# duobackpane.net
KiCad netlist of a schematic drawn in EAGLE
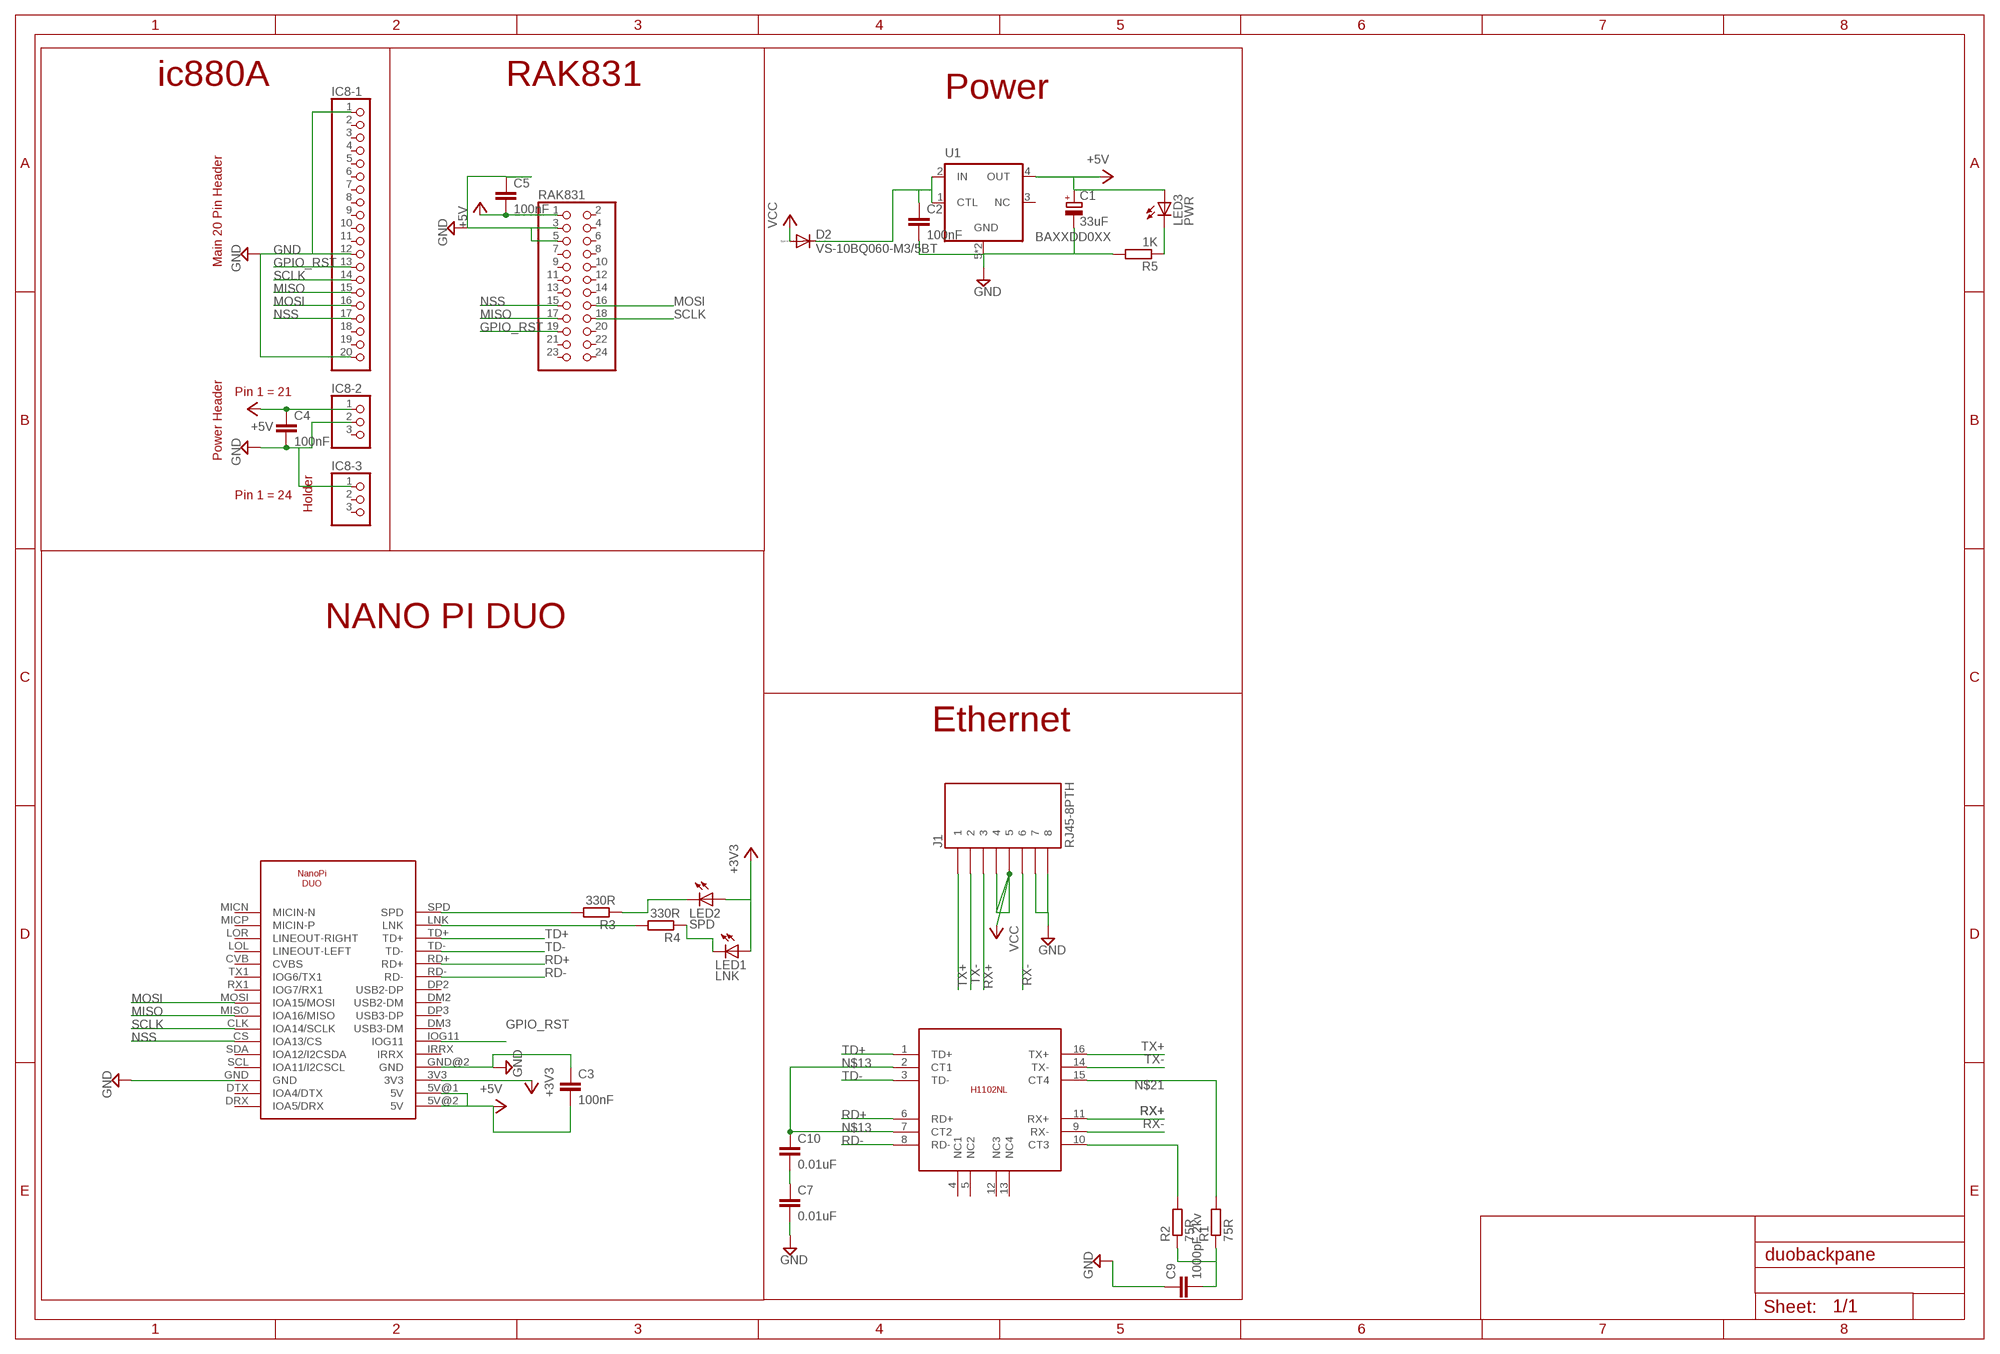
[diagram p0: schematic, sheet 1]

(export (version "E")
  (design (tool "Eeschema 10.0.6"))
  (components
    (comp (ref "C1")
      (value "33uF")
      (footprint "eagle-import:SMC_A")
      (libsource (lib "eagle-import") (part "CPOL-EUSMCA"))
    )
    (comp (ref "C2")
      (value "100nF")
      (footprint "eagle-import:C0805")
      (libsource (lib "eagle-import") (part "C-EUC0805"))
    )
    (comp (ref "C3")
      (value "100nF")
      (footprint "eagle-import:C0805")
      (libsource (lib "eagle-import") (part "C-EUC0805"))
    )
    (comp (ref "C4")
      (value "100nF")
      (footprint "eagle-import:C0805")
      (libsource (lib "eagle-import") (part "C-EUC0805"))
    )
    (comp (ref "C5")
      (value "100nF")
      (footprint "eagle-import:C0805")
      (libsource (lib "eagle-import") (part "C-EUC0805"))
    )
    (comp (ref "C7")
      (value "0.01uF")
      (footprint "eagle-import:C0805")
      (libsource (lib "eagle-import") (part "C-EUC0805"))
    )
    (comp (ref "C9")
      (value "1000pF 2kv")
      (footprint "eagle-import:C1206")
      (libsource (lib "eagle-import") (part "C-EUC1206"))
    )
    (comp (ref "C10")
      (value "0.01uF")
      (footprint "eagle-import:C0805")
      (libsource (lib "eagle-import") (part "C-EUC0805"))
    )
    (comp (ref "D2")
      (value "VS-10BQ060-M3/5BT")
      (footprint "eagle-import:DO214AA")
      (libsource (lib "eagle-import") (part "DIODE-DO214AA"))
    )
    (comp (ref "IC8-1")
      (value "PINHD-1X20")
      (footprint "eagle-import:1X20")
      (libsource (lib "eagle-import") (part "PINHD-1X20"))
    )
    (comp (ref "IC8-2")
      (value "PINHD-1X3")
      (footprint "eagle-import:1X03")
      (libsource (lib "eagle-import") (part "PINHD-1X3"))
    )
    (comp (ref "IC8-3")
      (value "PINHD-1X3")
      (footprint "eagle-import:1X03")
      (libsource (lib "eagle-import") (part "PINHD-1X3"))
    )
    (comp (ref "J1")
      (value "RJ45-8PTH")
      (footprint "eagle-import:RJ45-8")
      (libsource (lib "eagle-import") (part "RJ45-8PTH"))
    )
    (comp (ref "LED1")
      (value "LNK")
      (footprint "eagle-import:SML1206")
      (libsource (lib "eagle-import") (part "LEDSML1206"))
    )
    (comp (ref "LED2")
      (value "SPD")
      (footprint "eagle-import:SML1206")
      (libsource (lib "eagle-import") (part "LEDSML1206"))
    )
    (comp (ref "LED3")
      (value "PWR")
      (footprint "eagle-import:SML1206")
      (libsource (lib "eagle-import") (part "LEDSML1206"))
    )
    (comp (ref "R1")
      (value "75R")
      (footprint "eagle-import:R0805")
      (libsource (lib "eagle-import") (part "R-EU_R0805"))
    )
    (comp (ref "R2")
      (value "75R")
      (footprint "eagle-import:R0805")
      (libsource (lib "eagle-import") (part "R-EU_R0805"))
    )
    (comp (ref "R3")
      (value "330R")
      (footprint "eagle-import:R0805")
      (libsource (lib "eagle-import") (part "R-EU_R0805"))
    )
    (comp (ref "R4")
      (value "330R")
      (footprint "eagle-import:R0805")
      (libsource (lib "eagle-import") (part "R-EU_R0805"))
    )
    (comp (ref "R5")
      (value "1K")
      (footprint "eagle-import:R0805")
      (libsource (lib "eagle-import") (part "R-EU_R0805"))
    )
    (comp (ref "RAK831")
      (value "PINHD-2X12")
      (footprint "eagle-import:2X12")
      (libsource (lib "eagle-import") (part "PINHD-2X12"))
    )
    (comp (ref "U$1")
      (value "DECADE-H1102NL")
      (footprint "eagle-import:DECADE-H1102NL")
      (libsource (lib "eagle-import") (part "DECADE-H1102NL"))
    )
    (comp (ref "U$2")
      (value "NANOPIDUO")
      (footprint "eagle-import:NANOPIDUO")
      (libsource (lib "eagle-import") (part "NANOPIDUO"))
    )
    (comp (ref "U1")
      (value "BAXXDD0XX")
      (footprint "eagle-import:HRP5")
      (libsource (lib "eagle-import") (part "BAXXDD0XX"))
    )
  )
  (nets
    (net (code "1") (name "+3V3") (class "Default")
      (node (ref "LED1") (pin "A") (pinfunction "A_A") (pintype "passive"))
      (node (ref "LED2") (pin "A") (pinfunction "A_A") (pintype "passive"))
      (node (ref "U$2") (pin "3V3") (pinfunction "3V3_3V3") (pintype "bidirectional"))
    )
    (net (code "2") (name "+5V") (class "Default")
      (node (ref "C1") (pin "+") (pinfunction "+_+") (pintype "passive"))
      (node (ref "C3") (pin "2") (pinfunction "2_2") (pintype "passive"))
      (node (ref "C4") (pin "1") (pinfunction "1_1") (pintype "passive"))
      (node (ref "C5") (pin "2") (pinfunction "2_2") (pintype "passive"))
      (node (ref "IC8-2") (pin "1") (pinfunction "1_1") (pintype "passive"))
      (node (ref "LED3") (pin "A") (pinfunction "A_A") (pintype "passive"))
      (node (ref "RAK831") (pin "1") (pinfunction "1_1") (pintype "passive"))
      (node (ref "U$2") (pin "5V@1") (pinfunction "5V_5V@1") (pintype "bidirectional"))
      (node (ref "U$2") (pin "5V@2") (pinfunction "5V_5V@2") (pintype "bidirectional"))
      (node (ref "U1") (pin "4") (pinfunction "OUT_4") (pintype "passive"))
    )
    (net (code "3") (name "/GPIO_RST") (class "Default")
      (node (ref "IC8-1") (pin "13") (pinfunction "13_13") (pintype "passive"))
      (node (ref "RAK831") (pin "19") (pinfunction "19_19") (pintype "passive"))
      (node (ref "U$2") (pin "IOG11") (pinfunction "IOG11_IOG11") (pintype "bidirectional"))
    )
    (net (code "4") (name "/MISO") (class "Default")
      (node (ref "IC8-1") (pin "15") (pinfunction "15_15") (pintype "passive"))
      (node (ref "RAK831") (pin "17") (pinfunction "17_17") (pintype "passive"))
      (node (ref "U$2") (pin "MISO") (pinfunction "IOA16/MISO_MISO") (pintype "bidirectional"))
    )
    (net (code "5") (name "/MOSI") (class "Default")
      (node (ref "IC8-1") (pin "16") (pinfunction "16_16") (pintype "passive"))
      (node (ref "RAK831") (pin "16") (pinfunction "16_16") (pintype "passive"))
      (node (ref "U$2") (pin "MOSI") (pinfunction "IOA15/MOSI_MOSI") (pintype "bidirectional"))
    )
    (net (code "6") (name "/N$13") (class "Default")
      (node (ref "C10") (pin "1") (pinfunction "1_1") (pintype "passive"))
      (node (ref "U$1") (pin "2") (pinfunction "CT1_2") (pintype "bidirectional"))
      (node (ref "U$1") (pin "7") (pinfunction "CT2_7") (pintype "bidirectional"))
    )
    (net (code "7") (name "/N$21") (class "Default")
      (node (ref "R1") (pin "2") (pinfunction "2_2") (pintype "passive"))
      (node (ref "U$1") (pin "15") (pinfunction "CT4_15") (pintype "bidirectional"))
    )
    (net (code "8") (name "/NSS") (class "Default")
      (node (ref "IC8-1") (pin "17") (pinfunction "17_17") (pintype "passive"))
      (node (ref "RAK831") (pin "15") (pinfunction "15_15") (pintype "passive"))
      (node (ref "U$2") (pin "CS") (pinfunction "IOA13/CS_CS") (pintype "bidirectional"))
    )
    (net (code "9") (name "/RD+") (class "Default")
      (node (ref "U$1") (pin "6") (pinfunction "RD+_6") (pintype "bidirectional"))
      (node (ref "U$2") (pin "RD+") (pinfunction "RD+_RD+") (pintype "bidirectional"))
    )
    (net (code "10") (name "/RD-") (class "Default")
      (node (ref "U$1") (pin "8") (pinfunction "RD-_8") (pintype "bidirectional"))
      (node (ref "U$2") (pin "RD-") (pinfunction "RD-_RD-") (pintype "bidirectional"))
    )
    (net (code "11") (name "/RX+") (class "Default")
      (node (ref "J1") (pin "3") (pinfunction "3_3") (pintype "bidirectional"))
      (node (ref "U$1") (pin "11") (pinfunction "RX+_11") (pintype "bidirectional"))
    )
    (net (code "12") (name "/RX-") (class "Default")
      (node (ref "J1") (pin "6") (pinfunction "6_6") (pintype "bidirectional"))
      (node (ref "U$1") (pin "9") (pinfunction "RX-_9") (pintype "bidirectional"))
    )
    (net (code "13") (name "/SCLK") (class "Default")
      (node (ref "IC8-1") (pin "14") (pinfunction "14_14") (pintype "passive"))
      (node (ref "RAK831") (pin "18") (pinfunction "18_18") (pintype "passive"))
      (node (ref "U$2") (pin "CLK") (pinfunction "IOA14/SCLK_CLK") (pintype "bidirectional"))
    )
    (net (code "14") (name "/TD+") (class "Default")
      (node (ref "U$1") (pin "1") (pinfunction "TD+_1") (pintype "bidirectional"))
      (node (ref "U$2") (pin "TD+") (pinfunction "TD+_TD+") (pintype "bidirectional"))
    )
    (net (code "15") (name "/TD-") (class "Default")
      (node (ref "U$1") (pin "3") (pinfunction "TD-_3") (pintype "bidirectional"))
      (node (ref "U$2") (pin "TD-") (pinfunction "TD-_TD-") (pintype "bidirectional"))
    )
    (net (code "16") (name "/TX+") (class "Default")
      (node (ref "J1") (pin "1") (pinfunction "1_1") (pintype "bidirectional"))
      (node (ref "U$1") (pin "16") (pinfunction "TX+_16") (pintype "bidirectional"))
    )
    (net (code "17") (name "/TX-") (class "Default")
      (node (ref "J1") (pin "2") (pinfunction "2_2") (pintype "bidirectional"))
      (node (ref "U$1") (pin "14") (pinfunction "TX-_14") (pintype "bidirectional"))
    )
    (net (code "18") (name "GND") (class "Default")
      (node (ref "C1") (pin "-") (pinfunction "-_-") (pintype "passive"))
      (node (ref "C2") (pin "2") (pinfunction "2_2") (pintype "passive"))
      (node (ref "C3") (pin "1") (pinfunction "1_1") (pintype "passive"))
      (node (ref "C4") (pin "2") (pinfunction "2_2") (pintype "passive"))
      (node (ref "C5") (pin "1") (pinfunction "1_1") (pintype "passive"))
      (node (ref "C7") (pin "2") (pinfunction "2_2") (pintype "passive"))
      (node (ref "C9") (pin "1") (pinfunction "1_1") (pintype "passive"))
      (node (ref "IC8-1") (pin "1") (pinfunction "1_1") (pintype "passive"))
      (node (ref "IC8-1") (pin "12") (pinfunction "12_12") (pintype "passive"))
      (node (ref "IC8-1") (pin "20") (pinfunction "20_20") (pintype "passive"))
      (node (ref "IC8-2") (pin "2") (pinfunction "2_2") (pintype "passive"))
      (node (ref "IC8-3") (pin "1") (pinfunction "1_1") (pintype "passive"))
      (node (ref "J1") (pin "7") (pinfunction "7_7") (pintype "bidirectional"))
      (node (ref "J1") (pin "8") (pinfunction "8_8") (pintype "bidirectional"))
      (node (ref "R5") (pin "2") (pinfunction "2_2") (pintype "passive"))
      (node (ref "RAK831") (pin "3") (pinfunction "3_3") (pintype "passive"))
      (node (ref "RAK831") (pin "5") (pinfunction "5_5") (pintype "passive"))
      (node (ref "U$2") (pin "GND") (pinfunction "GND_GND") (pintype "bidirectional"))
      (node (ref "U$2") (pin "GND@2") (pinfunction "GND_GND@2") (pintype "bidirectional"))
      (node (ref "U1") (pin "5") (pinfunction "GND_5") (pintype "passive"))
      (node (ref "U1") (pin "6") (pinfunction "GND_6") (pintype "passive"))
    )
    (net (code "19") (name "Net-(C9-Pad2)") (class "Default")
      (node (ref "C9") (pin "2") (pinfunction "2_2") (pintype "passive"))
      (node (ref "R1") (pin "1") (pinfunction "1_1") (pintype "passive"))
      (node (ref "R2") (pin "1") (pinfunction "1_1") (pintype "passive"))
    )
    (net (code "20") (name "Net-(C10-Pad2)") (class "Default")
      (node (ref "C10") (pin "2") (pinfunction "2_2") (pintype "passive"))
      (node (ref "C7") (pin "1") (pinfunction "1_1") (pintype "passive"))
    )
    (net (code "21") (name "Net-(LED1-PadC)") (class "Default")
      (node (ref "LED1") (pin "C") (pinfunction "C_C") (pintype "passive"))
      (node (ref "R4") (pin "1") (pinfunction "1_1") (pintype "passive"))
    )
    (net (code "22") (name "Net-(LED2-PadC)") (class "Default")
      (node (ref "LED2") (pin "C") (pinfunction "C_C") (pintype "passive"))
      (node (ref "R3") (pin "1") (pinfunction "1_1") (pintype "passive"))
    )
    (net (code "23") (name "Net-(LED3-PadC)") (class "Default")
      (node (ref "LED3") (pin "C") (pinfunction "C_C") (pintype "passive"))
      (node (ref "R5") (pin "1") (pinfunction "1_1") (pintype "passive"))
    )
    (net (code "24") (name "Net-(R3-Pad2)") (class "Default")
      (node (ref "R3") (pin "2") (pinfunction "2_2") (pintype "passive"))
      (node (ref "U$2") (pin "SPD") (pinfunction "SPD_SPD") (pintype "bidirectional"))
    )
    (net (code "25") (name "Net-(R4-Pad2)") (class "Default")
      (node (ref "R4") (pin "2") (pinfunction "2_2") (pintype "passive"))
      (node (ref "U$2") (pin "LNK") (pinfunction "LNK_LNK") (pintype "bidirectional"))
    )
    (net (code "26") (name "Net-(U$1-CT3)") (class "Default")
      (node (ref "R2") (pin "2") (pinfunction "2_2") (pintype "passive"))
      (node (ref "U$1") (pin "10") (pinfunction "CT3_10") (pintype "bidirectional"))
    )
    (net (code "27") (name "Net-(U1-CTL)") (class "Default")
      (node (ref "C2") (pin "1") (pinfunction "1_1") (pintype "passive"))
      (node (ref "D2") (pin "C") (pinfunction "C_C") (pintype "passive"))
      (node (ref "U1") (pin "1") (pinfunction "CTL_1") (pintype "input"))
      (node (ref "U1") (pin "2") (pinfunction "IN_2") (pintype "input"))
    )
    (net (code "28") (name "VCC") (class "Default")
      (node (ref "D2") (pin "A") (pinfunction "A_A") (pintype "passive"))
      (node (ref "J1") (pin "4") (pinfunction "4_4") (pintype "bidirectional"))
      (node (ref "J1") (pin "5") (pinfunction "5_5") (pintype "bidirectional"))
    )
    (net (code "29") (name "unconnected-(IC8-1-Pad2)") (class "Default")
      (node (ref "IC8-1") (pin "2") (pinfunction "2_2") (pintype "passive"))
    )
    (net (code "30") (name "unconnected-(IC8-1-Pad3)") (class "Default")
      (node (ref "IC8-1") (pin "3") (pinfunction "3_3") (pintype "passive"))
    )
    (net (code "31") (name "unconnected-(IC8-1-Pad4)") (class "Default")
      (node (ref "IC8-1") (pin "4") (pinfunction "4_4") (pintype "passive"))
    )
    (net (code "32") (name "unconnected-(IC8-1-Pad5)") (class "Default")
      (node (ref "IC8-1") (pin "5") (pinfunction "5_5") (pintype "passive"))
    )
    (net (code "33") (name "unconnected-(IC8-1-Pad6)") (class "Default")
      (node (ref "IC8-1") (pin "6") (pinfunction "6_6") (pintype "passive"))
    )
    (net (code "34") (name "unconnected-(IC8-1-Pad7)") (class "Default")
      (node (ref "IC8-1") (pin "7") (pinfunction "7_7") (pintype "passive"))
    )
    (net (code "35") (name "unconnected-(IC8-1-Pad8)") (class "Default")
      (node (ref "IC8-1") (pin "8") (pinfunction "8_8") (pintype "passive"))
    )
    (net (code "36") (name "unconnected-(IC8-1-Pad9)") (class "Default")
      (node (ref "IC8-1") (pin "9") (pinfunction "9_9") (pintype "passive"))
    )
    (net (code "37") (name "unconnected-(IC8-1-Pad10)") (class "Default")
      (node (ref "IC8-1") (pin "10") (pinfunction "10_10") (pintype "passive"))
    )
    (net (code "38") (name "unconnected-(IC8-1-Pad11)") (class "Default")
      (node (ref "IC8-1") (pin "11") (pinfunction "11_11") (pintype "passive"))
    )
    (net (code "39") (name "unconnected-(IC8-1-Pad18)") (class "Default")
      (node (ref "IC8-1") (pin "18") (pinfunction "18_18") (pintype "passive"))
    )
    (net (code "40") (name "unconnected-(IC8-1-Pad19)") (class "Default")
      (node (ref "IC8-1") (pin "19") (pinfunction "19_19") (pintype "passive"))
    )
    (net (code "41") (name "unconnected-(IC8-2-Pad3)") (class "Default")
      (node (ref "IC8-2") (pin "3") (pinfunction "3_3") (pintype "passive"))
    )
    (net (code "42") (name "unconnected-(IC8-3-Pad2)") (class "Default")
      (node (ref "IC8-3") (pin "2") (pinfunction "2_2") (pintype "passive"))
    )
    (net (code "43") (name "unconnected-(IC8-3-Pad3)") (class "Default")
      (node (ref "IC8-3") (pin "3") (pinfunction "3_3") (pintype "passive"))
    )
    (net (code "44") (name "unconnected-(RAK831-Pad2)") (class "Default")
      (node (ref "RAK831") (pin "2") (pinfunction "2_2") (pintype "passive"))
    )
    (net (code "45") (name "unconnected-(RAK831-Pad4)") (class "Default")
      (node (ref "RAK831") (pin "4") (pinfunction "4_4") (pintype "passive"))
    )
    (net (code "46") (name "unconnected-(RAK831-Pad6)") (class "Default")
      (node (ref "RAK831") (pin "6") (pinfunction "6_6") (pintype "passive"))
    )
    (net (code "47") (name "unconnected-(RAK831-Pad7)") (class "Default")
      (node (ref "RAK831") (pin "7") (pinfunction "7_7") (pintype "passive"))
    )
    (net (code "48") (name "unconnected-(RAK831-Pad8)") (class "Default")
      (node (ref "RAK831") (pin "8") (pinfunction "8_8") (pintype "passive"))
    )
    (net (code "49") (name "unconnected-(RAK831-Pad9)") (class "Default")
      (node (ref "RAK831") (pin "9") (pinfunction "9_9") (pintype "passive"))
    )
    (net (code "50") (name "unconnected-(RAK831-Pad10)") (class "Default")
      (node (ref "RAK831") (pin "10") (pinfunction "10_10") (pintype "passive"))
    )
    (net (code "51") (name "unconnected-(RAK831-Pad11)") (class "Default")
      (node (ref "RAK831") (pin "11") (pinfunction "11_11") (pintype "passive"))
    )
    (net (code "52") (name "unconnected-(RAK831-Pad12)") (class "Default")
      (node (ref "RAK831") (pin "12") (pinfunction "12_12") (pintype "passive"))
    )
    (net (code "53") (name "unconnected-(RAK831-Pad13)") (class "Default")
      (node (ref "RAK831") (pin "13") (pinfunction "13_13") (pintype "passive"))
    )
    (net (code "54") (name "unconnected-(RAK831-Pad14)") (class "Default")
      (node (ref "RAK831") (pin "14") (pinfunction "14_14") (pintype "passive"))
    )
    (net (code "55") (name "unconnected-(RAK831-Pad20)") (class "Default")
      (node (ref "RAK831") (pin "20") (pinfunction "20_20") (pintype "passive"))
    )
    (net (code "56") (name "unconnected-(RAK831-Pad21)") (class "Default")
      (node (ref "RAK831") (pin "21") (pinfunction "21_21") (pintype "passive"))
    )
    (net (code "57") (name "unconnected-(RAK831-Pad22)") (class "Default")
      (node (ref "RAK831") (pin "22") (pinfunction "22_22") (pintype "passive"))
    )
    (net (code "58") (name "unconnected-(RAK831-Pad23)") (class "Default")
      (node (ref "RAK831") (pin "23") (pinfunction "23_23") (pintype "passive"))
    )
    (net (code "59") (name "unconnected-(RAK831-Pad24)") (class "Default")
      (node (ref "RAK831") (pin "24") (pinfunction "24_24") (pintype "passive"))
    )
    (net (code "60") (name "unconnected-(U$1-NC1-Pad4)") (class "Default")
      (node (ref "U$1") (pin "4") (pinfunction "NC1_4") (pintype "bidirectional"))
    )
    (net (code "61") (name "unconnected-(U$1-NC2-Pad5)") (class "Default")
      (node (ref "U$1") (pin "5") (pinfunction "NC2_5") (pintype "bidirectional"))
    )
    (net (code "62") (name "unconnected-(U$1-NC3-Pad12)") (class "Default")
      (node (ref "U$1") (pin "12") (pinfunction "NC3_12") (pintype "bidirectional"))
    )
    (net (code "63") (name "unconnected-(U$1-NC4-Pad13)") (class "Default")
      (node (ref "U$1") (pin "13") (pinfunction "NC4_13") (pintype "bidirectional"))
    )
    (net (code "64") (name "unconnected-(U$2-CVBS-PadCVB)") (class "Default")
      (node (ref "U$2") (pin "CVB") (pinfunction "CVBS_CVB") (pintype "bidirectional"))
    )
    (net (code "65") (name "unconnected-(U$2-IOA4{slash}DTX-PadDTX)") (class "Default")
      (node (ref "U$2") (pin "DTX") (pinfunction "IOA4/DTX_DTX") (pintype "bidirectional"))
    )
    (net (code "66") (name "unconnected-(U$2-IOA5{slash}DRX-PadDRX)") (class "Default")
      (node (ref "U$2") (pin "DRX") (pinfunction "IOA5/DRX_DRX") (pintype "bidirectional"))
    )
    (net (code "67") (name "unconnected-(U$2-IOA11{slash}I2CSCL-PadSCL)") (class "Default")
      (node (ref "U$2") (pin "SCL") (pinfunction "IOA11/I2CSCL_SCL") (pintype "bidirectional"))
    )
    (net (code "68") (name "unconnected-(U$2-IOA12{slash}I2CSDA-PadSDA)") (class "Default")
      (node (ref "U$2") (pin "SDA") (pinfunction "IOA12/I2CSDA_SDA") (pintype "bidirectional"))
    )
    (net (code "69") (name "unconnected-(U$2-IOG6{slash}TX1-PadTX1)") (class "Default")
      (node (ref "U$2") (pin "TX1") (pinfunction "IOG6/TX1_TX1") (pintype "bidirectional"))
    )
    (net (code "70") (name "unconnected-(U$2-IOG7{slash}RX1-PadRX1)") (class "Default")
      (node (ref "U$2") (pin "RX1") (pinfunction "IOG7/RX1_RX1") (pintype "bidirectional"))
    )
    (net (code "71") (name "unconnected-(U$2-LINEOUT-LEFT-PadLOL)") (class "Default")
      (node (ref "U$2") (pin "LOL") (pinfunction "LINEOUT-LEFT_LOL") (pintype "bidirectional"))
    )
    (net (code "72") (name "unconnected-(U$2-LINEOUT-RIGHT-PadLOR)") (class "Default")
      (node (ref "U$2") (pin "LOR") (pinfunction "LINEOUT-RIGHT_LOR") (pintype "bidirectional"))
    )
    (net (code "73") (name "unconnected-(U$2-MICIN-N-PadMICN)") (class "Default")
      (node (ref "U$2") (pin "MICN") (pinfunction "MICIN-N_MICN") (pintype "bidirectional"))
    )
    (net (code "74") (name "unconnected-(U$2-MICIN-P-PadMICP)") (class "Default")
      (node (ref "U$2") (pin "MICP") (pinfunction "MICIN-P_MICP") (pintype "bidirectional"))
    )
    (net (code "75") (name "unconnected-(U$2-PadIRRX)") (class "Default")
      (node (ref "U$2") (pin "IRRX") (pinfunction "IRRX_IRRX") (pintype "bidirectional"))
    )
    (net (code "76") (name "unconnected-(U$2-USB2-DM-PadDM2)") (class "Default")
      (node (ref "U$2") (pin "DM2") (pinfunction "USB2-DM_DM2") (pintype "bidirectional"))
    )
    (net (code "77") (name "unconnected-(U$2-USB2-DP-PadDP2)") (class "Default")
      (node (ref "U$2") (pin "DP2") (pinfunction "USB2-DP_DP2") (pintype "bidirectional"))
    )
    (net (code "78") (name "unconnected-(U$2-USB3-DM-PadDM3)") (class "Default")
      (node (ref "U$2") (pin "DM3") (pinfunction "USB3-DM_DM3") (pintype "bidirectional"))
    )
    (net (code "79") (name "unconnected-(U$2-USB3-DP-PadDP3)") (class "Default")
      (node (ref "U$2") (pin "DP3") (pinfunction "USB3-DP_DP3") (pintype "bidirectional"))
    )
    (net (code "80") (name "unconnected-(U1-NC-Pad3)") (class "Default")
      (node (ref "U1") (pin "3") (pinfunction "NC_3") (pintype "no_connect"))
    )
  )
)
